# START_VARIO.net
KiCad netlist of a schematic drawn in EAGLE
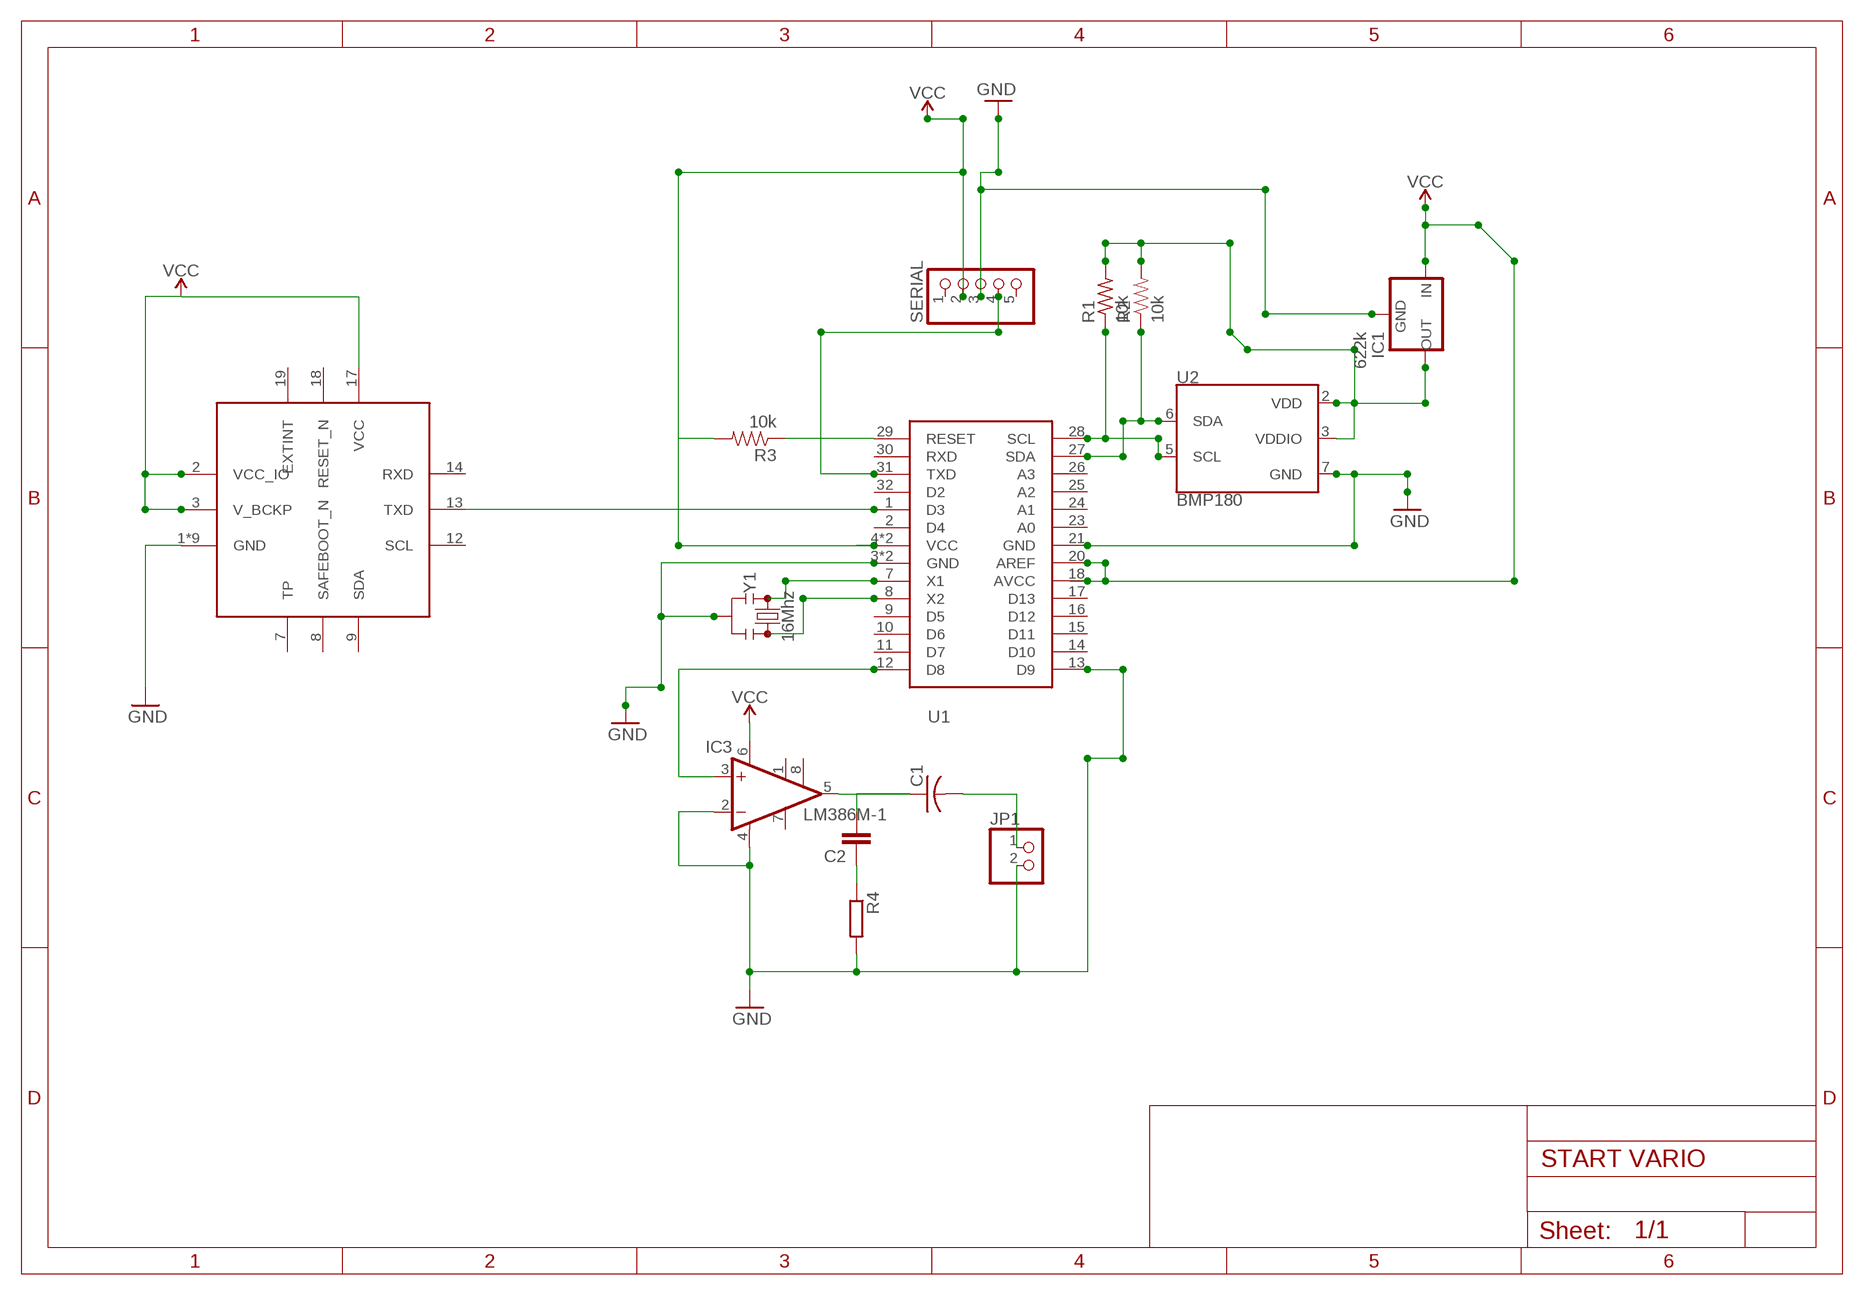
[diagram p0: schematic, sheet 1]

(export (version "E")
  (design (tool "Eeschema 10.0.6"))
  (components
    (comp (ref "C1")
      (value "C-USC1608")
      (footprint "eagle-import:C1608")
      (libsource (lib "eagle-import") (part "C-USC1608"))
    )
    (comp (ref "C2")
      (value "C-EUC0805")
      (footprint "eagle-import:C0805")
      (libsource (lib "eagle-import") (part "C-EUC0805"))
    )
    (comp (ref "IC1")
      (value "622k")
      (footprint "eagle-import:SOT23")
      (libsource (lib "eagle-import") (part "XC63FPM"))
    )
    (comp (ref "IC2")
      (value "SAM-M8Q")
      (footprint "eagle-import:SAM-M8Q")
      (libsource (lib "eagle-import") (part "SAM-M8Q"))
    )
    (comp (ref "IC3")
      (value "LM386M-1")
      (footprint "eagle-import:SO08")
      (libsource (lib "eagle-import") (part "LM386?-M1"))
    )
    (comp (ref "JP1")
      (value "PINHD-1X2")
      (footprint "eagle-import:1X02")
      (libsource (lib "eagle-import") (part "PINHD-1X2"))
    )
    (comp (ref "R1")
      (value "10k")
      (footprint "eagle-import:R0805")
      (libsource (lib "eagle-import") (part "R-US_R0805"))
    )
    (comp (ref "R2")
      (value "10k")
      (footprint "eagle-import:0603-RES")
      (libsource (lib "eagle-import") (part "RESISTOR0603-RES"))
    )
    (comp (ref "R3")
      (value "10k")
      (footprint "eagle-import:0603-RES")
      (libsource (lib "eagle-import") (part "RESISTOR0603-RES"))
    )
    (comp (ref "R4")
      (value "R-EU_R0805")
      (footprint "eagle-import:R0805")
      (libsource (lib "eagle-import") (part "R-EU_R0805"))
    )
    (comp (ref "SERIAL")
      (value "PINHD-1X5")
      (footprint "eagle-import:1X05")
      (libsource (lib "eagle-import") (part "PINHD-1X5"))
    )
    (comp (ref "U1")
      (value "ATMEGA328P")
      (footprint "eagle-import:TQFP32-08")
      (libsource (lib "eagle-import") (part "ATMEGA328P"))
    )
    (comp (ref "U2")
      (value "BMP180")
      (footprint "eagle-import:BMP180")
      (libsource (lib "eagle-import") (part "BMP180"))
    )
    (comp (ref "Y1")
      (value "16Mhz")
      (footprint "eagle-import:RESONATOR-SMD-3.2X1.3")
      (libsource (lib "eagle-import") (part "RESONATORSMD-3.2X1.3"))
    )
  )
  (nets
    (net (code "1") (name "GND") (class "Default")
      (node (ref "IC1") (pin "1") (pinfunction "GND_1") (pintype "input"))
      (node (ref "IC2") (pin "1") (pinfunction "GND_1") (pintype "bidirectional"))
      (node (ref "IC2") (pin "10") (pinfunction "GND_10") (pintype "bidirectional"))
      (node (ref "IC2") (pin "11") (pinfunction "GND_11") (pintype "bidirectional"))
      (node (ref "IC2") (pin "15") (pinfunction "GND_15") (pintype "bidirectional"))
      (node (ref "IC2") (pin "16") (pinfunction "GND_16") (pintype "bidirectional"))
      (node (ref "IC2") (pin "20") (pinfunction "GND_20") (pintype "bidirectional"))
      (node (ref "IC2") (pin "4") (pinfunction "GND_4") (pintype "bidirectional"))
      (node (ref "IC2") (pin "5") (pinfunction "GND_5") (pintype "bidirectional"))
      (node (ref "IC2") (pin "6") (pinfunction "GND_6") (pintype "bidirectional"))
      (node (ref "IC3") (pin "2") (pinfunction "-IN_2") (pintype "input"))
      (node (ref "IC3") (pin "4") (pinfunction "GND_4") (pintype "power_in"))
      (node (ref "JP1") (pin "2") (pinfunction "2_2") (pintype "passive"))
      (node (ref "R4") (pin "2") (pinfunction "2_2") (pintype "passive"))
      (node (ref "SERIAL") (pin "3") (pinfunction "3_3") (pintype "passive"))
      (node (ref "U1") (pin "13") (pinfunction "D9_13") (pintype "bidirectional"))
      (node (ref "U1") (pin "21") (pinfunction "GND_21") (pintype "bidirectional"))
      (node (ref "U1") (pin "3") (pinfunction "GND_3") (pintype "bidirectional"))
      (node (ref "U1") (pin "5") (pinfunction "GND_5") (pintype "bidirectional"))
      (node (ref "U2") (pin "7") (pinfunction "GND_7") (pintype "power_in"))
      (node (ref "Y1") (pin "2") (pinfunction "2_2") (pintype "passive"))
    )
    (net (code "2") (name "Net-(C1-Pad2)") (class "Default")
      (node (ref "C1") (pin "2") (pinfunction "2_2") (pintype "passive"))
      (node (ref "JP1") (pin "1") (pinfunction "1_1") (pintype "passive"))
    )
    (net (code "3") (name "Net-(C2-Pad1)") (class "Default")
      (node (ref "C2") (pin "1") (pinfunction "1_1") (pintype "passive"))
      (node (ref "R4") (pin "1") (pinfunction "1_1") (pintype "passive"))
    )
    (net (code "4") (name "Net-(IC1-OUT)") (class "Default")
      (node (ref "IC1") (pin "2") (pinfunction "OUT_2") (pintype "passive"))
      (node (ref "R1") (pin "2") (pinfunction "2_2") (pintype "passive"))
      (node (ref "R2") (pin "2") (pinfunction "2_2") (pintype "passive"))
      (node (ref "U2") (pin "2") (pinfunction "VDD_2") (pintype "power_in"))
      (node (ref "U2") (pin "3") (pinfunction "VDDIO_3") (pintype "power_in"))
    )
    (net (code "5") (name "Net-(IC2-TXD)") (class "Default")
      (node (ref "IC2") (pin "13") (pinfunction "TXD_13") (pintype "bidirectional"))
      (node (ref "U1") (pin "1") (pinfunction "D3_1") (pintype "bidirectional"))
    )
    (net (code "6") (name "Net-(IC3-+IN)") (class "Default")
      (node (ref "IC3") (pin "3") (pinfunction "+IN_3") (pintype "input"))
      (node (ref "U1") (pin "12") (pinfunction "D8_12") (pintype "bidirectional"))
    )
    (net (code "7") (name "Net-(IC3-OUT)") (class "Default")
      (node (ref "C1") (pin "1") (pinfunction "1_1") (pintype "passive"))
      (node (ref "C2") (pin "2") (pinfunction "2_2") (pintype "passive"))
      (node (ref "IC3") (pin "5") (pinfunction "OUT_5") (pintype "output"))
    )
    (net (code "8") (name "Net-(U1-RESET)") (class "Default")
      (node (ref "R3") (pin "1") (pinfunction "1_1") (pintype "passive"))
      (node (ref "U1") (pin "29") (pinfunction "RESET_29") (pintype "bidirectional"))
    )
    (net (code "9") (name "Net-(U1-SCL)") (class "Default")
      (node (ref "R1") (pin "1") (pinfunction "1_1") (pintype "passive"))
      (node (ref "U1") (pin "28") (pinfunction "SCL_28") (pintype "bidirectional"))
      (node (ref "U2") (pin "5") (pinfunction "SCL_5") (pintype "input"))
    )
    (net (code "10") (name "Net-(U1-SDA)") (class "Default")
      (node (ref "R2") (pin "1") (pinfunction "1_1") (pintype "passive"))
      (node (ref "U1") (pin "27") (pinfunction "SDA_27") (pintype "bidirectional"))
      (node (ref "U2") (pin "6") (pinfunction "SDA_6") (pintype "bidirectional"))
    )
    (net (code "11") (name "Net-(U1-TXD)") (class "Default")
      (node (ref "SERIAL") (pin "4") (pinfunction "4_4") (pintype "passive"))
      (node (ref "U1") (pin "31") (pinfunction "TXD_31") (pintype "bidirectional"))
    )
    (net (code "12") (name "Net-(U1-X1)") (class "Default")
      (node (ref "U1") (pin "7") (pinfunction "X1_7") (pintype "bidirectional"))
      (node (ref "Y1") (pin "1") (pinfunction "1_1") (pintype "passive"))
    )
    (net (code "13") (name "Net-(U1-X2)") (class "Default")
      (node (ref "U1") (pin "8") (pinfunction "X2_8") (pintype "bidirectional"))
      (node (ref "Y1") (pin "3") (pinfunction "3_3") (pintype "passive"))
    )
    (net (code "14") (name "VCC") (class "Default")
      (node (ref "IC1") (pin "3") (pinfunction "IN_3") (pintype "input"))
      (node (ref "IC2") (pin "17") (pinfunction "VCC_17") (pintype "bidirectional"))
      (node (ref "IC2") (pin "2") (pinfunction "VCC_IO_2") (pintype "bidirectional"))
      (node (ref "IC2") (pin "3") (pinfunction "V_BCKP_3") (pintype "bidirectional"))
      (node (ref "IC3") (pin "6") (pinfunction "VS_6") (pintype "power_in"))
      (node (ref "R3") (pin "2") (pinfunction "2_2") (pintype "passive"))
      (node (ref "SERIAL") (pin "2") (pinfunction "2_2") (pintype "passive"))
      (node (ref "U1") (pin "18") (pinfunction "AVCC_18") (pintype "bidirectional"))
      (node (ref "U1") (pin "20") (pinfunction "AREF_20") (pintype "bidirectional"))
      (node (ref "U1") (pin "4") (pinfunction "VCC_4") (pintype "bidirectional"))
      (node (ref "U1") (pin "6") (pinfunction "VCC_6") (pintype "bidirectional"))
    )
    (net (code "15") (name "unconnected-(IC2-EXTINT-Pad19)") (class "Default")
      (node (ref "IC2") (pin "19") (pinfunction "EXTINT_19") (pintype "bidirectional"))
    )
    (net (code "16") (name "unconnected-(IC2-RESET_N-Pad18)") (class "Default")
      (node (ref "IC2") (pin "18") (pinfunction "RESET_N_18") (pintype "bidirectional"))
    )
    (net (code "17") (name "unconnected-(IC2-RXD-Pad14)") (class "Default")
      (node (ref "IC2") (pin "14") (pinfunction "RXD_14") (pintype "bidirectional"))
    )
    (net (code "18") (name "unconnected-(IC2-SAFEBOOT_N-Pad8)") (class "Default")
      (node (ref "IC2") (pin "8") (pinfunction "SAFEBOOT_N_8") (pintype "bidirectional"))
    )
    (net (code "19") (name "unconnected-(IC2-SCL-Pad12)") (class "Default")
      (node (ref "IC2") (pin "12") (pinfunction "SCL_12") (pintype "bidirectional"))
    )
    (net (code "20") (name "unconnected-(IC2-SDA-Pad9)") (class "Default")
      (node (ref "IC2") (pin "9") (pinfunction "SDA_9") (pintype "bidirectional"))
    )
    (net (code "21") (name "unconnected-(IC2-TP-Pad7)") (class "Default")
      (node (ref "IC2") (pin "7") (pinfunction "TP_7") (pintype "bidirectional"))
    )
    (net (code "22") (name "unconnected-(IC3-BYPASS-Pad7)") (class "Default")
      (node (ref "IC3") (pin "7") (pinfunction "BYPASS_7") (pintype "passive"))
    )
    (net (code "23") (name "unconnected-(IC3-GAIN-Pad1)") (class "Default")
      (node (ref "IC3") (pin "1") (pinfunction "GAIN_1") (pintype "passive"))
    )
    (net (code "24") (name "unconnected-(IC3-GAIN-Pad8)") (class "Default")
      (node (ref "IC3") (pin "8") (pinfunction "GAIN_8") (pintype "passive"))
    )
    (net (code "25") (name "unconnected-(SERIAL-Pad1)") (class "Default")
      (node (ref "SERIAL") (pin "1") (pinfunction "1_1") (pintype "passive"))
    )
    (net (code "26") (name "unconnected-(SERIAL-Pad5)") (class "Default")
      (node (ref "SERIAL") (pin "5") (pinfunction "5_5") (pintype "passive"))
    )
    (net (code "27") (name "unconnected-(U1-A0-Pad23)") (class "Default")
      (node (ref "U1") (pin "23") (pinfunction "A0_23") (pintype "bidirectional"))
    )
    (net (code "28") (name "unconnected-(U1-A1-Pad24)") (class "Default")
      (node (ref "U1") (pin "24") (pinfunction "A1_24") (pintype "bidirectional"))
    )
    (net (code "29") (name "unconnected-(U1-A2-Pad25)") (class "Default")
      (node (ref "U1") (pin "25") (pinfunction "A2_25") (pintype "bidirectional"))
    )
    (net (code "30") (name "unconnected-(U1-A3-Pad26)") (class "Default")
      (node (ref "U1") (pin "26") (pinfunction "A3_26") (pintype "bidirectional"))
    )
    (net (code "31") (name "unconnected-(U1-D2-Pad32)") (class "Default")
      (node (ref "U1") (pin "32") (pinfunction "D2_32") (pintype "bidirectional"))
    )
    (net (code "32") (name "unconnected-(U1-D4-Pad2)") (class "Default")
      (node (ref "U1") (pin "2") (pinfunction "D4_2") (pintype "bidirectional"))
    )
    (net (code "33") (name "unconnected-(U1-D5-Pad9)") (class "Default")
      (node (ref "U1") (pin "9") (pinfunction "D5_9") (pintype "bidirectional"))
    )
    (net (code "34") (name "unconnected-(U1-D6-Pad10)") (class "Default")
      (node (ref "U1") (pin "10") (pinfunction "D6_10") (pintype "bidirectional"))
    )
    (net (code "35") (name "unconnected-(U1-D7-Pad11)") (class "Default")
      (node (ref "U1") (pin "11") (pinfunction "D7_11") (pintype "bidirectional"))
    )
    (net (code "36") (name "unconnected-(U1-D10-Pad14)") (class "Default")
      (node (ref "U1") (pin "14") (pinfunction "D10_14") (pintype "bidirectional"))
    )
    (net (code "37") (name "unconnected-(U1-D11-Pad15)") (class "Default")
      (node (ref "U1") (pin "15") (pinfunction "D11_15") (pintype "bidirectional"))
    )
    (net (code "38") (name "unconnected-(U1-D12-Pad16)") (class "Default")
      (node (ref "U1") (pin "16") (pinfunction "D12_16") (pintype "bidirectional"))
    )
    (net (code "39") (name "unconnected-(U1-D13-Pad17)") (class "Default")
      (node (ref "U1") (pin "17") (pinfunction "D13_17") (pintype "bidirectional"))
    )
    (net (code "40") (name "unconnected-(U1-RXD-Pad30)") (class "Default")
      (node (ref "U1") (pin "30") (pinfunction "RXD_30") (pintype "bidirectional"))
    )
  )
)
